# OutProtect.net
KiCad netlist of a schematic drawn in Altium Designer
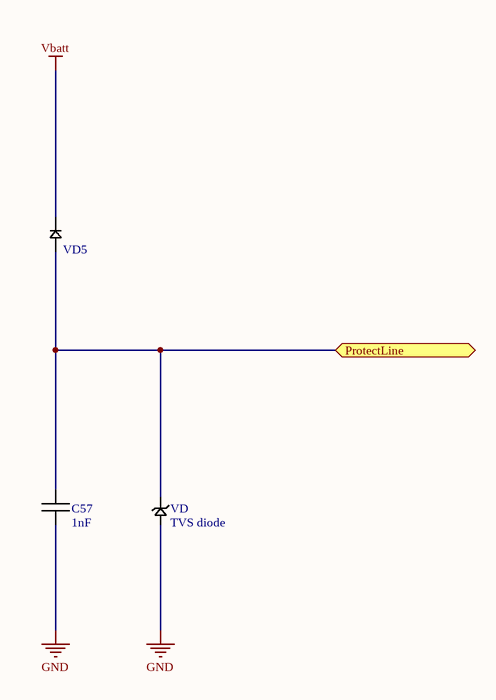
[diagram p0: OutProtect.SchDoc]

(export (version "E")
  (design (tool "Eeschema 10.0.6"))
  (components
    (comp (ref "C57")
      (value "1nF")
      (footprint "SMD 0603")
      (description "CC0603KRX7R9BB102")
      (libsource (lib "Maks_lib") (part "Capasitor"))
    )
    (comp (ref "VD")
      (value "TVS diode")
      (footprint "SOD323")
      (description "CDSOD323-T18LC")
      (libsource (lib "Maks_lib") (part "TVS diode"))
    )
    (comp (ref "VD5")
      (value "Diode")
      (footprint "SOD323")
      (description "PMEG2020EJ.115")
      (libsource (lib "Maks_lib") (part "Diode"))
    )
  )
  (nets
    (net (code "1") (name "/ProtectLine") (class "Default")
      (node (ref "C57") (pin "2") (pinfunction "2_2") (pintype "passive"))
      (node (ref "VD") (pin "1") (pinfunction "1_1") (pintype "passive"))
      (node (ref "VD5") (pin "0") (pinfunction "0_0") (pintype "passive"))
    )
    (net (code "2") (name "GND") (class "Default")
      (node (ref "C57") (pin "1") (pinfunction "1_1") (pintype "passive"))
      (node (ref "VD") (pin "2") (pinfunction "2_2") (pintype "passive"))
    )
    (net (code "3") (name "Vbatt") (class "Default")
      (node (ref "VD5") (pin "1") (pinfunction "1_1") (pintype "passive"))
    )
  )
)
